# MICROCONTROLLER.net
KiCad netlist of a schematic drawn in Altium Designer
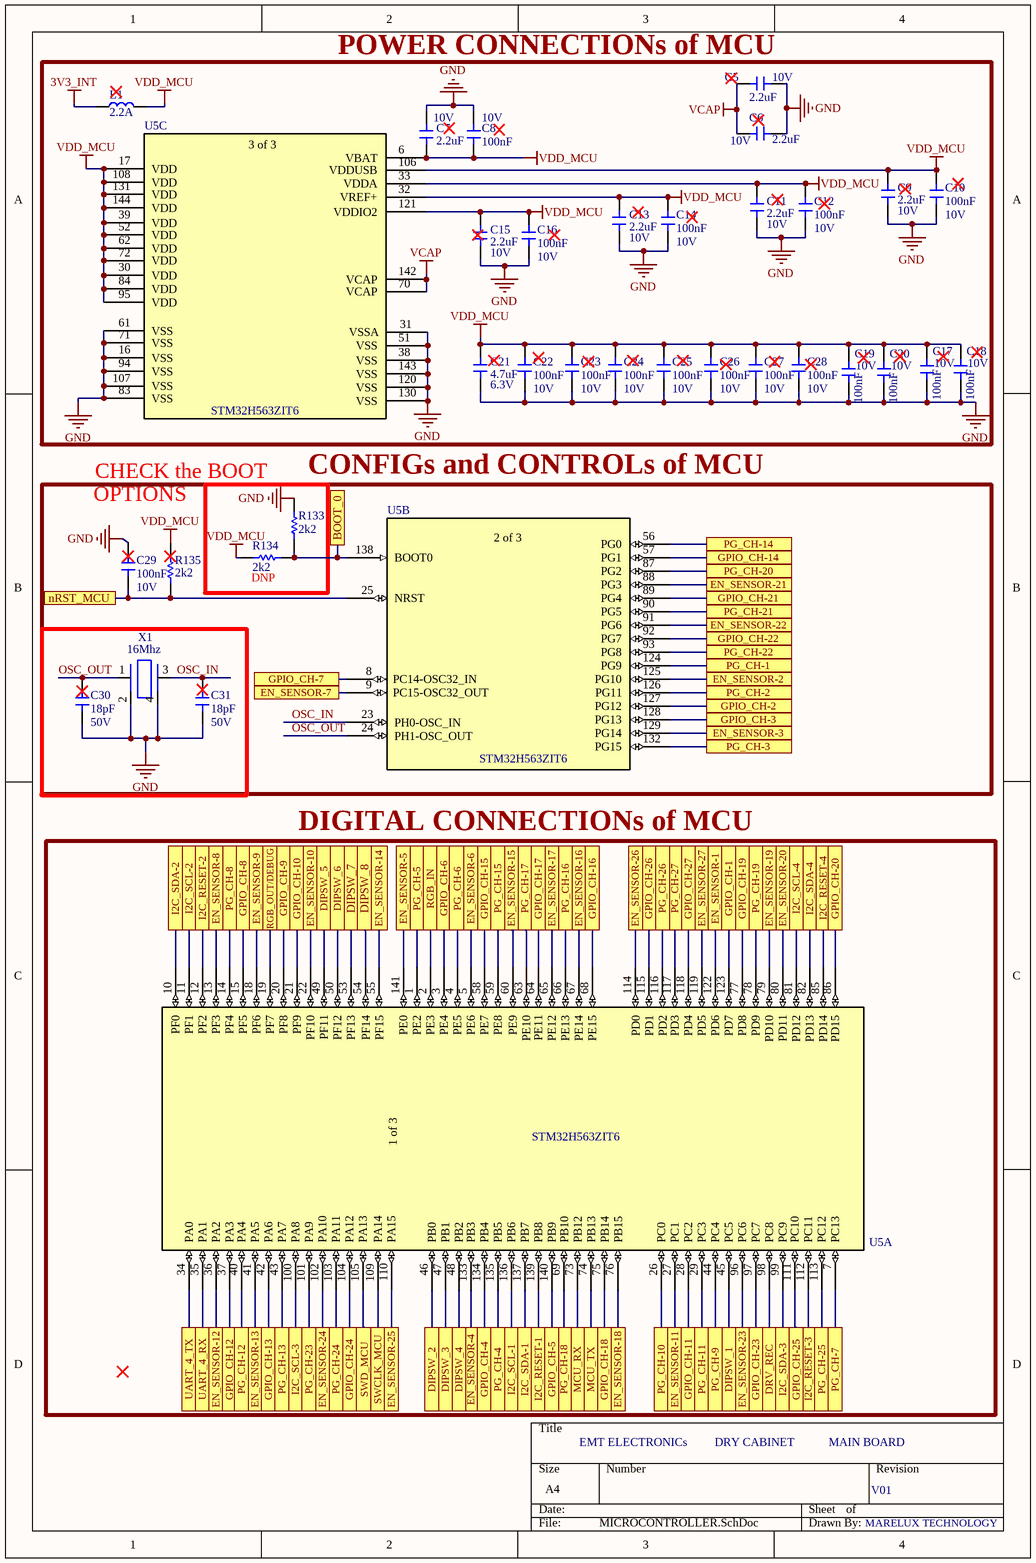
[diagram p0: MICROCONTROLLER.SchDoc]

(export (version "E")
  (design (tool "Eeschema 10.0.6"))
  (components
    (comp (ref "C5")
      (value "2.2uF")
      (footprint "MareLux24Lib:CAP_0603_CER")
      (description "2.2uF 0603 Ceramic Capacitor")
      (fields (field (name "PART NUMBER") "CL10A225KP8NNNC") (field (name "VOLTAGE") "10V"))
      (libsource (lib "MareLux24Lib") (part "CAP_GEN_CER"))
    )
    (comp (ref "C6")
      (value "2.2uF")
      (footprint "MareLux24Lib:CAP_0603_CER")
      (description "2.2uF 0603 Ceramic Capacitor")
      (fields (field (name "PART NUMBER") "CL10A225KP8NNNC") (field (name "VOLTAGE") "10V"))
      (libsource (lib "MareLux24Lib") (part "CAP_GEN_CER"))
    )
    (comp (ref "C7")
      (value "2.2uF")
      (footprint "MareLux24Lib:CAP_0603_CER")
      (description "2.2uF 0603 Ceramic Capacitor")
      (fields (field (name "PART NUMBER") "CL10A225KP8NNNC") (field (name "VOLTAGE") "10V"))
      (libsource (lib "MareLux24Lib") (part "CAP_GEN_CER"))
    )
    (comp (ref "C8")
      (value "100nF")
      (footprint "MareLux24Lib:CAP_0402_CER")
      (description "100nF 0402 Ceramic Capacitor")
      (fields (field (name "PART NUMBER") "CL05B104KP5NNNC") (field (name "VOLTAGE") "10V"))
      (libsource (lib "MareLux24Lib") (part "CAP_GEN_CER"))
    )
    (comp (ref "C9")
      (value "2.2uF")
      (footprint "MareLux24Lib:CAP_0603_CER")
      (description "2.2uF 0603 Ceramic Capacitor")
      (fields (field (name "PART NUMBER") "CL10A225KP8NNNC") (field (name "VOLTAGE") "10V"))
      (libsource (lib "MareLux24Lib") (part "CAP_GEN_CER"))
    )
    (comp (ref "C10")
      (value "100nF")
      (footprint "MareLux24Lib:CAP_0402_CER")
      (description "100nF 0402 Ceramic Capacitor")
      (fields (field (name "PART NUMBER") "CL05B104KP5NNNC") (field (name "VOLTAGE") "10V"))
      (libsource (lib "MareLux24Lib") (part "CAP_GEN_CER"))
    )
    (comp (ref "C11")
      (value "2.2uF")
      (footprint "MareLux24Lib:CAP_0603_CER")
      (description "2.2uF 0603 Ceramic Capacitor")
      (fields (field (name "PART NUMBER") "CL10A225KP8NNNC") (field (name "VOLTAGE") "10V"))
      (libsource (lib "MareLux24Lib") (part "CAP_GEN_CER"))
    )
    (comp (ref "C12")
      (value "100nF")
      (footprint "MareLux24Lib:CAP_0402_CER")
      (description "100nF 0402 Ceramic Capacitor")
      (fields (field (name "PART NUMBER") "CL05B104KP5NNNC") (field (name "VOLTAGE") "10V"))
      (libsource (lib "MareLux24Lib") (part "CAP_GEN_CER"))
    )
    (comp (ref "C13")
      (value "2.2uF")
      (footprint "MareLux24Lib:CAP_0603_CER")
      (description "2.2uF 0603 Ceramic Capacitor")
      (fields (field (name "PART NUMBER") "CL10A225KP8NNNC") (field (name "VOLTAGE") "10V"))
      (libsource (lib "MareLux24Lib") (part "CAP_GEN_CER"))
    )
    (comp (ref "C14")
      (value "100nF")
      (footprint "MareLux24Lib:CAP_0402_CER")
      (description "100nF 0402 Ceramic Capacitor")
      (fields (field (name "PART NUMBER") "CL05B104KP5NNNC") (field (name "VOLTAGE") "10V"))
      (libsource (lib "MareLux24Lib") (part "CAP_GEN_CER"))
    )
    (comp (ref "C15")
      (value "2.2uF")
      (footprint "MareLux24Lib:CAP_0603_CER")
      (description "2.2uF 0603 Ceramic Capacitor")
      (fields (field (name "PART NUMBER") "CL10A225KP8NNNC") (field (name "VOLTAGE") "10V"))
      (libsource (lib "MareLux24Lib") (part "CAP_GEN_CER"))
    )
    (comp (ref "C16")
      (value "100nF")
      (footprint "MareLux24Lib:CAP_0402_CER")
      (description "100nF 0402 Ceramic Capacitor")
      (fields (field (name "PART NUMBER") "CL05B104KP5NNNC") (field (name "VOLTAGE") "10V"))
      (libsource (lib "MareLux24Lib") (part "CAP_GEN_CER"))
    )
    (comp (ref "C17")
      (value "100nF")
      (footprint "MareLux24Lib:CAP_0402_CER")
      (description "100nF 0402 Ceramic Capacitor")
      (fields (field (name "PART NUMBER") "CL05B104KP5NNNC") (field (name "VOLTAGE") "10V"))
      (libsource (lib "MareLux24Lib") (part "CAP_GEN_CER"))
    )
    (comp (ref "C18")
      (value "100nF")
      (footprint "MareLux24Lib:CAP_0402_CER")
      (description "100nF 0402 Ceramic Capacitor")
      (fields (field (name "PART NUMBER") "CL05B104KP5NNNC") (field (name "VOLTAGE") "10V"))
      (libsource (lib "MareLux24Lib") (part "CAP_GEN_CER"))
    )
    (comp (ref "C19")
      (value "100nF")
      (footprint "MareLux24Lib:CAP_0402_CER")
      (description "100nF 0402 Ceramic Capacitor")
      (fields (field (name "PART NUMBER") "CL05B104KP5NNNC") (field (name "VOLTAGE") "10V"))
      (libsource (lib "MareLux24Lib") (part "CAP_GEN_CER"))
    )
    (comp (ref "C20")
      (value "100nF")
      (footprint "MareLux24Lib:CAP_0402_CER")
      (description "100nF 0402 Ceramic Capacitor")
      (fields (field (name "PART NUMBER") "CL05B104KP5NNNC") (field (name "VOLTAGE") "10V"))
      (libsource (lib "MareLux24Lib") (part "CAP_GEN_CER"))
    )
    (comp (ref "C21")
      (value "4.7uF")
      (footprint "MareLux24Lib:CAP_0603_CER")
      (description "4,7uF 0603 Ceramic Capacitor")
      (fields (field (name "PART NUMBER") "CL10A475KP8NNNC") (field (name "VOLTAGE") "6.3V"))
      (libsource (lib "MareLux24Lib") (part "CAP_GEN_CER"))
    )
    (comp (ref "C22")
      (value "100nF")
      (footprint "MareLux24Lib:CAP_0402_CER")
      (description "100nF 0402 Ceramic Capacitor")
      (fields (field (name "PART NUMBER") "CL05B104KP5NNNC") (field (name "VOLTAGE") "10V"))
      (libsource (lib "MareLux24Lib") (part "CAP_GEN_CER"))
    )
    (comp (ref "C23")
      (value "100nF")
      (footprint "MareLux24Lib:CAP_0402_CER")
      (description "100nF 0402 Ceramic Capacitor")
      (fields (field (name "PART NUMBER") "CL05B104KP5NNNC") (field (name "VOLTAGE") "10V"))
      (libsource (lib "MareLux24Lib") (part "CAP_GEN_CER"))
    )
    (comp (ref "C24")
      (value "100nF")
      (footprint "MareLux24Lib:CAP_0402_CER")
      (description "100nF 0402 Ceramic Capacitor")
      (fields (field (name "PART NUMBER") "CL05B104KP5NNNC") (field (name "VOLTAGE") "10V"))
      (libsource (lib "MareLux24Lib") (part "CAP_GEN_CER"))
    )
    (comp (ref "C25")
      (value "100nF")
      (footprint "MareLux24Lib:CAP_0402_CER")
      (description "100nF 0402 Ceramic Capacitor")
      (fields (field (name "PART NUMBER") "CL05B104KP5NNNC") (field (name "VOLTAGE") "10V"))
      (libsource (lib "MareLux24Lib") (part "CAP_GEN_CER"))
    )
    (comp (ref "C26")
      (value "100nF")
      (footprint "MareLux24Lib:CAP_0402_CER")
      (description "100nF 0402 Ceramic Capacitor")
      (fields (field (name "PART NUMBER") "CL05B104KP5NNNC") (field (name "VOLTAGE") "10V"))
      (libsource (lib "MareLux24Lib") (part "CAP_GEN_CER"))
    )
    (comp (ref "C27")
      (value "100nF")
      (footprint "MareLux24Lib:CAP_0402_CER")
      (description "100nF 0402 Ceramic Capacitor")
      (fields (field (name "PART NUMBER") "CL05B104KP5NNNC") (field (name "VOLTAGE") "10V"))
      (libsource (lib "MareLux24Lib") (part "CAP_GEN_CER"))
    )
    (comp (ref "C28")
      (value "100nF")
      (footprint "MareLux24Lib:CAP_0402_CER")
      (description "100nF 0402 Ceramic Capacitor")
      (fields (field (name "PART NUMBER") "CL05B104KP5NNNC") (field (name "VOLTAGE") "10V"))
      (libsource (lib "MareLux24Lib") (part "CAP_GEN_CER"))
    )
    (comp (ref "C29")
      (value "100nF")
      (footprint "MareLux24Lib:CAP_0402_CER")
      (description "100nF 0402 Ceramic Capacitor")
      (fields (field (name "PART NUMBER") "CL05B104KP5NNNC") (field (name "VOLTAGE") "10V"))
      (libsource (lib "MareLux24Lib") (part "CAP_GEN_CER"))
    )
    (comp (ref "C30")
      (value "18pF")
      (footprint "MareLux24Lib:CAP_0402_CER")
      (description "18pF 0402 Ceramic Capacitor")
      (fields (field (name "PART NUMBER") "CC0402JRNPO9BN180") (field (name "VOLTAGE") "50V"))
      (libsource (lib "MareLux24Lib") (part "CAP_GEN_CER"))
    )
    (comp (ref "C31")
      (value "18pF")
      (footprint "MareLux24Lib:CAP_0402_CER")
      (description "18pF 0402 Ceramic Capacitor")
      (fields (field (name "PART NUMBER") "CC0402JRNPO9BN180") (field (name "VOLTAGE") "50V"))
      (libsource (lib "MareLux24Lib") (part "CAP_GEN_CER"))
    )
    (comp (ref "L1")
      (value "MPZ1608S221ATA00")
      (footprint "IND_0603_SMD")
      (description "Generic SMD IND/BEAD")
      (fields (field (name "POWER") "2.2A") (field (name "MANUFACTURER") "TDK"))
      (libsource (lib "MareLux24Lib") (part "IND_GEN_SMD"))
    )
    (comp (ref "R133")
      (value "2k2")
      (footprint "MareLux24Lib:RES_0402_SMD")
      (description "Generic Chip Res 2k2")
      (fields (field (name "PART NUMBER") "RMCF0402JT2K20") (field (name "TOLERANCE") "5 %"))
      (libsource (lib "MareLux24Lib") (part "RES_GEN_SMD"))
    )
    (comp (ref "R134")
      (value "2k2")
      (footprint "MareLux24Lib:RES_0402_SMD")
      (description "Generic Chip Res 2k2")
      (fields
        (field (name "PART NUMBER") "RMCF0402JT2K20")
        (field (name "TOLERANCE") "5 %")
        (field (name "PLACE") "DNP")
      )
      (libsource (lib "MareLux24Lib") (part "RES_GEN_SMD"))
    )
    (comp (ref "R135")
      (value "2k2")
      (footprint "MareLux24Lib:RES_0402_SMD")
      (description "Generic Chip Res 2k2")
      (fields (field (name "PART NUMBER") "RMCF0402JT2K20") (field (name "TOLERANCE") "5 %"))
      (libsource (lib "MareLux24Lib") (part "RES_GEN_SMD"))
    )
    (comp (ref "U5")
      (value "STM32H563ZIT6")
      (footprint "LQFP-144")
      (description "ARM® Cortex®-M33 STM32H5 Microcontroller IC 32-Bit 250MHz 2MB (2M x 8) FLASH 144-LQFP (20x20)\r\n)")
      (fields (field (name "VOLTAGE") "1.7-3.6 V") (field (name "MANUFACTURER") "STM"))
      (libsource (lib "") (part "STM32H563ZIT6_2"))
    )
    (comp (ref "X1")
      (value "16Mhz")
      (footprint "XTAL-4SMD")
      (description "16 MHz ±10ppm Crystal 9pF 40 Ohms 4-SMD, No Lead")
      (fields (field (name "TOLERANCE") "±10ppm") (field (name "PART NUMBER") "CF4016M00009T1521005"))
      (libsource (lib "MareLux24Lib") (part "XTAL-4PINs"))
    )
  )
  (nets
    (net (code "1") (name "/BOOT_0") (class "Default")
      (node (ref "R133") (pin "2") (pinfunction "2_2") (pintype "passive"))
      (node (ref "R134") (pin "1") (pinfunction "1_1") (pintype "passive"))
      (node (ref "U5") (pin "138") (pinfunction "BOOT0_138") (pintype "input"))
    )
    (net (code "2") (name "/DIPSW_1") (class "Default")
      (node (ref "U5") (pin "45") (pinfunction "PC5_45") (pintype "bidirectional"))
    )
    (net (code "3") (name "/DIPSW_2") (class "Default")
      (node (ref "U5") (pin "46") (pinfunction "PB0_46") (pintype "bidirectional"))
    )
    (net (code "4") (name "/DIPSW_3") (class "Default")
      (node (ref "U5") (pin "47") (pinfunction "PB1_47") (pintype "bidirectional"))
    )
    (net (code "5") (name "/DIPSW_4") (class "Default")
      (node (ref "U5") (pin "48") (pinfunction "PB2_48") (pintype "bidirectional"))
    )
    (net (code "6") (name "/DIPSW_5") (class "Default")
      (node (ref "U5") (pin "49") (pinfunction "PF11_49") (pintype "bidirectional"))
    )
    (net (code "7") (name "/DIPSW_6") (class "Default")
      (node (ref "U5") (pin "50") (pinfunction "PF12_50") (pintype "bidirectional"))
    )
    (net (code "8") (name "/DIPSW_7") (class "Default")
      (node (ref "U5") (pin "53") (pinfunction "PF13_53") (pintype "bidirectional"))
    )
    (net (code "9") (name "/DIPSW_8") (class "Default")
      (node (ref "U5") (pin "54") (pinfunction "PF14_54") (pintype "bidirectional"))
    )
    (net (code "10") (name "/DRV_REC") (class "Default")
      (node (ref "U5") (pin "98") (pinfunction "PC8_98") (pintype "bidirectional"))
    )
    (net (code "11") (name "/EN_SENSOR-1") (class "Default")
      (node (ref "U5") (pin "122") (pinfunction "PD6_122") (pintype "bidirectional"))
    )
    (net (code "12") (name "/EN_SENSOR-2") (class "Default")
      (node (ref "U5") (pin "125") (pinfunction "PG10_125") (pintype "bidirectional"))
    )
    (net (code "13") (name "/EN_SENSOR-3") (class "Default")
      (node (ref "U5") (pin "129") (pinfunction "PG14_129") (pintype "bidirectional"))
    )
    (net (code "14") (name "/EN_SENSOR-4") (class "Default")
      (node (ref "U5") (pin "133") (pinfunction "PB3_133") (pintype "bidirectional"))
    )
    (net (code "15") (name "/EN_SENSOR-5") (class "Default")
      (node (ref "U5") (pin "141") (pinfunction "PE0_141") (pintype "bidirectional"))
    )
    (net (code "16") (name "/EN_SENSOR-6") (class "Default")
      (node (ref "U5") (pin "5") (pinfunction "PE6_5") (pintype "bidirectional"))
    )
    (net (code "17") (name "/EN_SENSOR-7") (class "Default")
      (node (ref "U5") (pin "9") (pinfunction "PC15-OSC32_OUT_9") (pintype "bidirectional"))
    )
    (net (code "18") (name "/EN_SENSOR-8") (class "Default")
      (node (ref "U5") (pin "13") (pinfunction "PF3_13") (pintype "bidirectional"))
    )
    (net (code "19") (name "/EN_SENSOR-9") (class "Default")
      (node (ref "U5") (pin "18") (pinfunction "PF6_18") (pintype "bidirectional"))
    )
    (net (code "20") (name "/EN_SENSOR-10") (class "Default")
      (node (ref "U5") (pin "22") (pinfunction "PF10_22") (pintype "bidirectional"))
    )
    (net (code "21") (name "/EN_SENSOR-11") (class "Default")
      (node (ref "U5") (pin "27") (pinfunction "PC1_27") (pintype "bidirectional"))
    )
    (net (code "22") (name "/EN_SENSOR-12") (class "Default")
      (node (ref "U5") (pin "36") (pinfunction "PA2_36") (pintype "bidirectional"))
    )
    (net (code "23") (name "/EN_SENSOR-13") (class "Default")
      (node (ref "U5") (pin "41") (pinfunction "PA5_41") (pintype "bidirectional"))
    )
    (net (code "24") (name "/EN_SENSOR-14") (class "Default")
      (node (ref "U5") (pin "55") (pinfunction "PF15_55") (pintype "bidirectional"))
    )
    (net (code "25") (name "/EN_SENSOR-15") (class "Default")
      (node (ref "U5") (pin "60") (pinfunction "PE9_60") (pintype "bidirectional"))
    )
    (net (code "26") (name "/EN_SENSOR-16") (class "Default")
      (node (ref "U5") (pin "67") (pinfunction "PE14_67") (pintype "bidirectional"))
    )
    (net (code "27") (name "/EN_SENSOR-17") (class "Default")
      (node (ref "U5") (pin "65") (pinfunction "PE12_65") (pintype "bidirectional"))
    )
    (net (code "28") (name "/EN_SENSOR-18") (class "Default")
      (node (ref "U5") (pin "76") (pinfunction "PB15_76") (pintype "bidirectional"))
    )
    (net (code "29") (name "/EN_SENSOR-19") (class "Default")
      (node (ref "U5") (pin "79") (pinfunction "PD10_79") (pintype "bidirectional"))
    )
    (net (code "30") (name "/EN_SENSOR-20") (class "Default")
      (node (ref "U5") (pin "80") (pinfunction "PD11_80") (pintype "bidirectional"))
    )
    (net (code "31") (name "/EN_SENSOR-21") (class "Default")
      (node (ref "U5") (pin "88") (pinfunction "PG3_88") (pintype "bidirectional"))
    )
    (net (code "32") (name "/EN_SENSOR-22") (class "Default")
      (node (ref "U5") (pin "91") (pinfunction "PG6_91") (pintype "bidirectional"))
    )
    (net (code "33") (name "/EN_SENSOR-23") (class "Default")
      (node (ref "U5") (pin "96") (pinfunction "PC6_96") (pintype "bidirectional"))
    )
    (net (code "34") (name "/EN_SENSOR-24") (class "Default")
      (node (ref "U5") (pin "102") (pinfunction "PA10_102") (pintype "bidirectional"))
    )
    (net (code "35") (name "/EN_SENSOR-25") (class "Default")
      (node (ref "U5") (pin "110") (pinfunction "PA15_110") (pintype "bidirectional"))
    )
    (net (code "36") (name "/EN_SENSOR-26") (class "Default")
      (node (ref "U5") (pin "114") (pinfunction "PD0_114") (pintype "bidirectional"))
    )
    (net (code "37") (name "/EN_SENSOR-27") (class "Default")
      (node (ref "U5") (pin "119") (pinfunction "PD5_119") (pintype "bidirectional"))
    )
    (net (code "38") (name "/GPIO_CH-1") (class "Default")
      (node (ref "U5") (pin "123") (pinfunction "PD7_123") (pintype "bidirectional"))
    )
    (net (code "39") (name "/GPIO_CH-2") (class "Default")
      (node (ref "U5") (pin "127") (pinfunction "PG12_127") (pintype "bidirectional"))
    )
    (net (code "40") (name "/GPIO_CH-3") (class "Default")
      (node (ref "U5") (pin "128") (pinfunction "PG13_128") (pintype "bidirectional"))
    )
    (net (code "41") (name "/GPIO_CH-4") (class "Default")
      (node (ref "U5") (pin "134") (pinfunction "PB4_134") (pintype "bidirectional"))
    )
    (net (code "42") (name "/GPIO_CH-5") (class "Default")
      (node (ref "U5") (pin "140") (pinfunction "PB9_140") (pintype "bidirectional"))
    )
    (net (code "43") (name "/GPIO_CH-6") (class "Default")
      (node (ref "U5") (pin "3") (pinfunction "PE4_3") (pintype "bidirectional"))
    )
    (net (code "44") (name "/GPIO_CH-7") (class "Default")
      (node (ref "U5") (pin "8") (pinfunction "PC14-OSC32_IN_8") (pintype "bidirectional"))
    )
    (net (code "45") (name "/GPIO_CH-8") (class "Default")
      (node (ref "U5") (pin "15") (pinfunction "PF5_15") (pintype "bidirectional"))
    )
    (net (code "46") (name "/GPIO_CH-9") (class "Default")
      (node (ref "U5") (pin "20") (pinfunction "PF8_20") (pintype "bidirectional"))
    )
    (net (code "47") (name "/GPIO_CH-10") (class "Default")
      (node (ref "U5") (pin "21") (pinfunction "PF9_21") (pintype "bidirectional"))
    )
    (net (code "48") (name "/GPIO_CH-11") (class "Default")
      (node (ref "U5") (pin "28") (pinfunction "PC2_28") (pintype "bidirectional"))
    )
    (net (code "49") (name "/GPIO_CH-12") (class "Default")
      (node (ref "U5") (pin "37") (pinfunction "PA3_37") (pintype "bidirectional"))
    )
    (net (code "50") (name "/GPIO_CH-13") (class "Default")
      (node (ref "U5") (pin "42") (pinfunction "PA6_42") (pintype "bidirectional"))
    )
    (net (code "51") (name "/GPIO_CH-14") (class "Default")
      (node (ref "U5") (pin "57") (pinfunction "PG1_57") (pintype "bidirectional"))
    )
    (net (code "52") (name "/GPIO_CH-15") (class "Default")
      (node (ref "U5") (pin "58") (pinfunction "PE7_58") (pintype "bidirectional"))
    )
    (net (code "53") (name "/GPIO_CH-16") (class "Default")
      (node (ref "U5") (pin "68") (pinfunction "PE15_68") (pintype "bidirectional"))
    )
    (net (code "54") (name "/GPIO_CH-17") (class "Default")
      (node (ref "U5") (pin "64") (pinfunction "PE11_64") (pintype "bidirectional"))
    )
    (net (code "55") (name "/GPIO_CH-18") (class "Default")
      (node (ref "U5") (pin "75") (pinfunction "PB14_75") (pintype "bidirectional"))
    )
    (net (code "56") (name "/GPIO_CH-19") (class "Default")
      (node (ref "U5") (pin "77") (pinfunction "PD8_77") (pintype "bidirectional"))
    )
    (net (code "57") (name "/GPIO_CH-20") (class "Default")
      (node (ref "U5") (pin "86") (pinfunction "PD15_86") (pintype "bidirectional"))
    )
    (net (code "58") (name "/GPIO_CH-21") (class "Default")
      (node (ref "U5") (pin "89") (pinfunction "PG4_89") (pintype "bidirectional"))
    )
    (net (code "59") (name "/GPIO_CH-22") (class "Default")
      (node (ref "U5") (pin "92") (pinfunction "PG7_92") (pintype "bidirectional"))
    )
    (net (code "60") (name "/GPIO_CH-23") (class "Default")
      (node (ref "U5") (pin "97") (pinfunction "PC7_97") (pintype "bidirectional"))
    )
    (net (code "61") (name "/GPIO_CH-24") (class "Default")
      (node (ref "U5") (pin "104") (pinfunction "PA12_104") (pintype "bidirectional"))
    )
    (net (code "62") (name "/GPIO_CH-25") (class "Default")
      (node (ref "U5") (pin "111") (pinfunction "PC10_111") (pintype "bidirectional"))
    )
    (net (code "63") (name "/GPIO_CH-26") (class "Default")
      (node (ref "U5") (pin "115") (pinfunction "PD1_115") (pintype "bidirectional"))
    )
    (net (code "64") (name "/GPIO_CH-27") (class "Default")
      (node (ref "U5") (pin "118") (pinfunction "PD4_118") (pintype "bidirectional"))
    )
    (net (code "65") (name "/I2C_RESET-1") (class "Default")
      (node (ref "U5") (pin "139") (pinfunction "PB8_139") (pintype "bidirectional"))
    )
    (net (code "66") (name "/I2C_RESET-2") (class "Default")
      (node (ref "U5") (pin "12") (pinfunction "PF2_12") (pintype "bidirectional"))
    )
    (net (code "67") (name "/I2C_RESET-3") (class "Default")
      (node (ref "U5") (pin "112") (pinfunction "PC11_112") (pintype "bidirectional"))
    )
    (net (code "68") (name "/I2C_RESET-4") (class "Default")
      (node (ref "U5") (pin "85") (pinfunction "PD14_85") (pintype "bidirectional"))
    )
    (net (code "69") (name "/I2C_SCL-1") (class "Default")
      (node (ref "U5") (pin "136") (pinfunction "PB6_136") (pintype "bidirectional"))
    )
    (net (code "70") (name "/I2C_SCL-2") (class "Default")
      (node (ref "U5") (pin "11") (pinfunction "PF1_11") (pintype "bidirectional"))
    )
    (net (code "71") (name "/I2C_SCL-3") (class "Default")
      (node (ref "U5") (pin "100") (pinfunction "PA8_100") (pintype "bidirectional"))
    )
    (net (code "72") (name "/I2C_SCL-4") (class "Default")
      (node (ref "U5") (pin "81") (pinfunction "PD12_81") (pintype "bidirectional"))
    )
    (net (code "73") (name "/I2C_SDA-1") (class "Default")
      (node (ref "U5") (pin "137") (pinfunction "PB7_137") (pintype "bidirectional"))
    )
    (net (code "74") (name "/I2C_SDA-2") (class "Default")
      (node (ref "U5") (pin "10") (pinfunction "PF0_10") (pintype "bidirectional"))
    )
    (net (code "75") (name "/I2C_SDA-3") (class "Default")
      (node (ref "U5") (pin "99") (pinfunction "PC9_99") (pintype "bidirectional"))
    )
    (net (code "76") (name "/I2C_SDA-4") (class "Default")
      (node (ref "U5") (pin "82") (pinfunction "PD13_82") (pintype "bidirectional"))
    )
    (net (code "77") (name "/MCU_RX") (class "Default")
      (node (ref "U5") (pin "73") (pinfunction "PB12_73") (pintype "bidirectional"))
    )
    (net (code "78") (name "/MCU_TX") (class "Default")
      (node (ref "U5") (pin "74") (pinfunction "PB13_74") (pintype "bidirectional"))
    )
    (net (code "79") (name "/OSC_IN") (class "Default")
      (node (ref "C31") (pin "1") (pinfunction "1_1") (pintype "passive"))
      (node (ref "U5") (pin "23") (pinfunction "PH0-OSC_IN_23") (pintype "bidirectional"))
      (node (ref "X1") (pin "3") (pinfunction "3_3") (pintype "passive"))
    )
    (net (code "80") (name "/OSC_OUT") (class "Default")
      (node (ref "C30") (pin "1") (pinfunction "1_1") (pintype "passive"))
      (node (ref "U5") (pin "24") (pinfunction "PH1-OSC_OUT_24") (pintype "bidirectional"))
      (node (ref "X1") (pin "1") (pinfunction "0_1") (pintype "passive"))
    )
    (net (code "81") (name "/PG_CH-1") (class "Default")
      (node (ref "U5") (pin "124") (pinfunction "PG9_124") (pintype "bidirectional"))
    )
    (net (code "82") (name "/PG_CH-2") (class "Default")
      (node (ref "U5") (pin "126") (pinfunction "PG11_126") (pintype "bidirectional"))
    )
    (net (code "83") (name "/PG_CH-3") (class "Default")
      (node (ref "U5") (pin "132") (pinfunction "PG15_132") (pintype "bidirectional"))
    )
    (net (code "84") (name "/PG_CH-4") (class "Default")
      (node (ref "U5") (pin "135") (pinfunction "PB5_135") (pintype "bidirectional"))
    )
    (net (code "85") (name "/PG_CH-5") (class "Default")
      (node (ref "U5") (pin "1") (pinfunction "PE2_1") (pintype "bidirectional"))
    )
    (net (code "86") (name "/PG_CH-6") (class "Default")
      (node (ref "U5") (pin "4") (pinfunction "PE5_4") (pintype "bidirectional"))
    )
    (net (code "87") (name "/PG_CH-7") (class "Default")
      (node (ref "U5") (pin "7") (pinfunction "PC13_7") (pintype "bidirectional"))
    )
    (net (code "88") (name "/PG_CH-8") (class "Default")
      (node (ref "U5") (pin "14") (pinfunction "PF4_14") (pintype "bidirectional"))
    )
    (net (code "89") (name "/PG_CH-9") (class "Default")
      (node (ref "U5") (pin "44") (pinfunction "PC4_44") (pintype "bidirectional"))
    )
    (net (code "90") (name "/PG_CH-10") (class "Default")
      (node (ref "U5") (pin "26") (pinfunction "PC0_26") (pintype "bidirectional"))
    )
    (net (code "91") (name "/PG_CH-11") (class "Default")
      (node (ref "U5") (pin "29") (pinfunction "PC3_29") (pintype "bidirectional"))
    )
    (net (code "92") (name "/PG_CH-12") (class "Default")
      (node (ref "U5") (pin "40") (pinfunction "PA4_40") (pintype "bidirectional"))
    )
    (net (code "93") (name "/PG_CH-13") (class "Default")
      (node (ref "U5") (pin "43") (pinfunction "PA7_43") (pintype "bidirectional"))
    )
    (net (code "94") (name "/PG_CH-14") (class "Default")
      (node (ref "U5") (pin "56") (pinfunction "PG0_56") (pintype "bidirectional"))
    )
    (net (code "95") (name "/PG_CH-15") (class "Default")
      (node (ref "U5") (pin "59") (pinfunction "PE8_59") (pintype "bidirectional"))
    )
    (net (code "96") (name "/PG_CH-16") (class "Default")
      (node (ref "U5") (pin "66") (pinfunction "PE13_66") (pintype "bidirectional"))
    )
    (net (code "97") (name "/PG_CH-17") (class "Default")
      (node (ref "U5") (pin "63") (pinfunction "PE10_63") (pintype "bidirectional"))
    )
    (net (code "98") (name "/PG_CH-18") (class "Default")
      (node (ref "U5") (pin "69") (pinfunction "PB10_69") (pintype "bidirectional"))
    )
    (net (code "99") (name "/PG_CH-19") (class "Default")
      (node (ref "U5") (pin "78") (pinfunction "PD9_78") (pintype "bidirectional"))
    )
    (net (code "100") (name "/PG_CH-20") (class "Default")
      (node (ref "U5") (pin "87") (pinfunction "PG2_87") (pintype "bidirectional"))
    )
    (net (code "101") (name "/PG_CH-21") (class "Default")
      (node (ref "U5") (pin "90") (pinfunction "PG5_90") (pintype "bidirectional"))
    )
    (net (code "102") (name "/PG_CH-22") (class "Default")
      (node (ref "U5") (pin "93") (pinfunction "PG8_93") (pintype "bidirectional"))
    )
    (net (code "103") (name "/PG_CH-23") (class "Default")
      (node (ref "U5") (pin "101") (pinfunction "PA9_101") (pintype "bidirectional"))
    )
    (net (code "104") (name "/PG_CH-24") (class "Default")
      (node (ref "U5") (pin "103") (pinfunction "PA11_103") (pintype "bidirectional"))
    )
    (net (code "105") (name "/PG_CH-25") (class "Default")
      (node (ref "U5") (pin "113") (pinfunction "PC12_113") (pintype "bidirectional"))
    )
    (net (code "106") (name "/PG_CH-26") (class "Default")
      (node (ref "U5") (pin "116") (pinfunction "PD2_116") (pintype "bidirectional"))
    )
    (net (code "107") (name "/PG_CH-27") (class "Default")
      (node (ref "U5") (pin "117") (pinfunction "PD3_117") (pintype "bidirectional"))
    )
    (net (code "108") (name "/RGB_IN") (class "Default")
      (node (ref "U5") (pin "2") (pinfunction "PE3_2") (pintype "bidirectional"))
    )
    (net (code "109") (name "/RGB_OUT{slash}DEBUG") (class "Default")
      (node (ref "U5") (pin "19") (pinfunction "PF7_19") (pintype "bidirectional"))
    )
    (net (code "110") (name "/SWCLK_MCU") (class "Default")
      (node (ref "U5") (pin "109") (pinfunction "PA14_109") (pintype "bidirectional"))
    )
    (net (code "111") (name "/SWD_MCU") (class "Default")
      (node (ref "U5") (pin "105") (pinfunction "PA13_105") (pintype "bidirectional"))
    )
    (net (code "112") (name "/UART_4_RX") (class "Default")
      (node (ref "U5") (pin "35") (pinfunction "PA1_35") (pintype "bidirectional"))
    )
    (net (code "113") (name "/UART_4_TX") (class "Default")
      (node (ref "U5") (pin "34") (pinfunction "PA0_34") (pintype "bidirectional"))
    )
    (net (code "114") (name "/nRST_MCU") (class "Default")
      (node (ref "C29") (pin "2") (pinfunction "2_2") (pintype "passive"))
      (node (ref "R135") (pin "1") (pinfunction "1_1") (pintype "passive"))
      (node (ref "U5") (pin "25") (pinfunction "NRST_25") (pintype "bidirectional"))
    )
    (net (code "115") (name "3V3_INT") (class "Default")
      (node (ref "L1") (pin "1") (pinfunction "1_1") (pintype "passive"))
    )
    (net (code "116") (name "GND") (class "Default")
      (node (ref "C10") (pin "2") (pinfunction "2_2") (pintype "passive"))
      (node (ref "C11") (pin "1") (pinfunction "1_1") (pintype "passive"))
      (node (ref "C12") (pin "2") (pinfunction "2_2") (pintype "passive"))
      (node (ref "C13") (pin "1") (pinfunction "1_1") (pintype "passive"))
      (node (ref "C14") (pin "2") (pinfunction "2_2") (pintype "passive"))
      (node (ref "C15") (pin "1") (pinfunction "1_1") (pintype "passive"))
      (node (ref "C16") (pin "2") (pinfunction "2_2") (pintype "passive"))
      (node (ref "C17") (pin "2") (pinfunction "2_2") (pintype "passive"))
      (node (ref "C18") (pin "2") (pinfunction "2_2") (pintype "passive"))
      (node (ref "C19") (pin "2") (pinfunction "2_2") (pintype "passive"))
      (node (ref "C20") (pin "2") (pinfunction "2_2") (pintype "passive"))
      (node (ref "C21") (pin "1") (pinfunction "1_1") (pintype "passive"))
      (node (ref "C22") (pin "2") (pinfunction "2_2") (pintype "passive"))
      (node (ref "C23") (pin "2") (pinfunction "2_2") (pintype "passive"))
      (node (ref "C24") (pin "2") (pinfunction "2_2") (pintype "passive"))
      (node (ref "C25") (pin "2") (pinfunction "2_2") (pintype "passive"))
      (node (ref "C26") (pin "2") (pinfunction "2_2") (pintype "passive"))
      (node (ref "C27") (pin "2") (pinfunction "2_2") (pintype "passive"))
      (node (ref "C28") (pin "2") (pinfunction "2_2") (pintype "passive"))
      (node (ref "C29") (pin "1") (pinfunction "1_1") (pintype "passive"))
      (node (ref "C30") (pin "2") (pinfunction "2_2") (pintype "passive"))
      (node (ref "C31") (pin "2") (pinfunction "2_2") (pintype "passive"))
      (node (ref "C5") (pin "1") (pinfunction "1_1") (pintype "passive"))
      (node (ref "C6") (pin "1") (pinfunction "1_1") (pintype "passive"))
      (node (ref "C7") (pin "2") (pinfunction "2_2") (pintype "passive"))
      (node (ref "C8") (pin "1") (pinfunction "1_1") (pintype "passive"))
      (node (ref "C9") (pin "1") (pinfunction "1_1") (pintype "passive"))
      (node (ref "R133") (pin "1") (pinfunction "1_1") (pintype "passive"))
      (node (ref "U5") (pin "107") (pinfunction "VSS_107") (pintype "power_in"))
      (node (ref "U5") (pin "120") (pinfunction "VSS_120") (pintype "power_in"))
      (node (ref "U5") (pin "130") (pinfunction "VSS_130") (pintype "power_in"))
      (node (ref "U5") (pin "143") (pinfunction "VSS_143") (pintype "power_in"))
      (node (ref "U5") (pin "16") (pinfunction "VSS_16") (pintype "power_in"))
      (node (ref "U5") (pin "31") (pinfunction "VSSA_31") (pintype "power_in"))
      (node (ref "U5") (pin "38") (pinfunction "VSS_38") (pintype "power_in"))
      (node (ref "U5") (pin "51") (pinfunction "VSS_51") (pintype "power_in"))
      (node (ref "U5") (pin "61") (pinfunction "VSS_61") (pintype "power_in"))
      (node (ref "U5") (pin "71") (pinfunction "VSS_71") (pintype "power_in"))
      (node (ref "U5") (pin "83") (pinfunction "VSS_83") (pintype "power_in"))
      (node (ref "U5") (pin "94") (pinfunction "VSS_94") (pintype "power_in"))
      (node (ref "X1") (pin "2") (pinfunction "2_2") (pintype "passive"))
      (node (ref "X1") (pin "4") (pinfunction "4_4") (pintype "passive"))
    )
    (net (code "117") (name "VCAP") (class "Default")
      (node (ref "C5") (pin "2") (pinfunction "2_2") (pintype "passive"))
      (node (ref "C6") (pin "2") (pinfunction "2_2") (pintype "passive"))
      (node (ref "U5") (pin "142") (pinfunction "VCAP_142") (pintype "power_in"))
      (node (ref "U5") (pin "70") (pinfunction "VCAP_70") (pintype "power_in"))
    )
    (net (code "118") (name "VDD_MCU") (class "Default")
      (node (ref "C10") (pin "1") (pinfunction "1_1") (pintype "passive"))
      (node (ref "C11") (pin "2") (pinfunction "2_2") (pintype "passive"))
      (node (ref "C12") (pin "1") (pinfunction "1_1") (pintype "passive"))
      (node (ref "C13") (pin "2") (pinfunction "2_2") (pintype "passive"))
      (node (ref "C14") (pin "1") (pinfunction "1_1") (pintype "passive"))
      (node (ref "C15") (pin "2") (pinfunction "2_2") (pintype "passive"))
      (node (ref "C16") (pin "1") (pinfunction "1_1") (pintype "passive"))
      (node (ref "C17") (pin "1") (pinfunction "1_1") (pintype "passive"))
      (node (ref "C18") (pin "1") (pinfunction "1_1") (pintype "passive"))
      (node (ref "C19") (pin "1") (pinfunction "1_1") (pintype "passive"))
      (node (ref "C20") (pin "1") (pinfunction "1_1") (pintype "passive"))
      (node (ref "C21") (pin "2") (pinfunction "2_2") (pintype "passive"))
      (node (ref "C22") (pin "1") (pinfunction "1_1") (pintype "passive"))
      (node (ref "C23") (pin "1") (pinfunction "1_1") (pintype "passive"))
      (node (ref "C24") (pin "1") (pinfunction "1_1") (pintype "passive"))
      (node (ref "C25") (pin "1") (pinfunction "1_1") (pintype "passive"))
      (node (ref "C26") (pin "1") (pinfunction "1_1") (pintype "passive"))
      (node (ref "C27") (pin "1") (pinfunction "1_1") (pintype "passive"))
      (node (ref "C28") (pin "1") (pinfunction "1_1") (pintype "passive"))
      (node (ref "C7") (pin "1") (pinfunction "1_1") (pintype "passive"))
      (node (ref "C8") (pin "2") (pinfunction "2_2") (pintype "passive"))
      (node (ref "C9") (pin "2") (pinfunction "2_2") (pintype "passive"))
      (node (ref "L1") (pin "2") (pinfunction "2_2") (pintype "passive"))
      (node (ref "R134") (pin "2") (pinfunction "2_2") (pintype "passive"))
      (node (ref "R135") (pin "2") (pinfunction "2_2") (pintype "passive"))
      (node (ref "U5") (pin "106") (pinfunction "VDDUSB_106") (pintype "power_in"))
      (node (ref "U5") (pin "108") (pinfunction "VDD_108") (pintype "power_in"))
      (node (ref "U5") (pin "121") (pinfunction "VDDIO2_121") (pintype "power_in"))
      (node (ref "U5") (pin "131") (pinfunction "VDD_131") (pintype "power_in"))
      (node (ref "U5") (pin "144") (pinfunction "VDD_144") (pintype "power_in"))
      (node (ref "U5") (pin "17") (pinfunction "VDD_17") (pintype "power_in"))
      (node (ref "U5") (pin "30") (pinfunction "VDD_30") (pintype "power_in"))
      (node (ref "U5") (pin "32") (pinfunction "VREF+_32") (pintype "power_in"))
      (node (ref "U5") (pin "33") (pinfunction "VDDA_33") (pintype "power_in"))
      (node (ref "U5") (pin "39") (pinfunction "VDD_39") (pintype "power_in"))
      (node (ref "U5") (pin "52") (pinfunction "VDD_52") (pintype "power_in"))
      (node (ref "U5") (pin "6") (pinfunction "VBAT_6") (pintype "power_in"))
      (node (ref "U5") (pin "62") (pinfunction "VDD_62") (pintype "power_in"))
      (node (ref "U5") (pin "72") (pinfunction "VDD_72") (pintype "power_in"))
      (node (ref "U5") (pin "84") (pinfunction "VDD_84") (pintype "power_in"))
      (node (ref "U5") (pin "95") (pinfunction "VDD_95") (pintype "power_in"))
    )
  )
)
